# Schematics.net
KiCad netlist of a schematic drawn in EAGLE
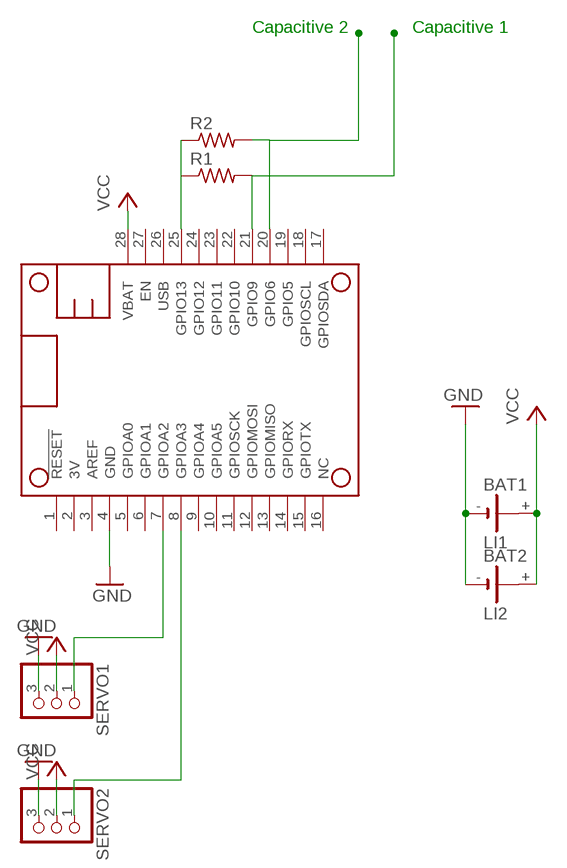
[diagram p0: schematic, sheet 1]

(export (version "E")
  (design (tool "Eeschema 10.0.6"))
  (components
    (comp (ref "BAT1")
      (value "LI1")
      (footprint "eagle-import:CR1_2")
      (libsource (lib "eagle-import") (part "CR1/2"))
    )
    (comp (ref "BAT2")
      (value "LI2")
      (footprint "eagle-import:CR1_2")
      (libsource (lib "eagle-import") (part "CR1/2"))
    )
    (comp (ref "MS1")
      (value "FEATHERWING")
      (footprint "eagle-import:FEATHERWING")
      (libsource (lib "eagle-import") (part "FEATHERWING"))
    )
    (comp (ref "R1")
      (value "R-US_0411/12")
      (footprint "eagle-import:0411_12")
      (libsource (lib "eagle-import") (part "R-US_0411/12"))
    )
    (comp (ref "R2")
      (value "R-US_0411/12")
      (footprint "eagle-import:0411_12")
      (libsource (lib "eagle-import") (part "R-US_0411/12"))
    )
    (comp (ref "SERVO1")
      (value "PINHD-1X3")
      (footprint "eagle-import:1X03")
      (libsource (lib "eagle-import") (part "PINHD-1X3"))
    )
    (comp (ref "SERVO2")
      (value "PINHD-1X3")
      (footprint "eagle-import:1X03")
      (libsource (lib "eagle-import") (part "PINHD-1X3"))
    )
  )
  (nets
    (net (code "1") (name "/3V") (class "Default")
      (node (ref "MS1") (pin "2") (pinfunction "3V_2") (pintype "power_in"))
    )
    (net (code "2") (name "/USB") (class "Default")
      (node (ref "MS1") (pin "26") (pinfunction "USB_26") (pintype "power_in"))
    )
    (net (code "3") (name "GND") (class "Default")
      (node (ref "BAT1") (pin "-") (pinfunction "-_-") (pintype "passive"))
      (node (ref "BAT2") (pin "-") (pinfunction "-_-") (pintype "passive"))
      (node (ref "MS1") (pin "4") (pinfunction "GND_4") (pintype "power_in"))
      (node (ref "SERVO1") (pin "3") (pinfunction "3_3") (pintype "passive"))
      (node (ref "SERVO2") (pin "3") (pinfunction "3_3") (pintype "passive"))
    )
    (net (code "4") (name "Net-(MS1-GPIO6)") (class "Default")
      (node (ref "MS1") (pin "20") (pinfunction "GPIO6_20") (pintype "bidirectional"))
      (node (ref "R2") (pin "2") (pinfunction "2_2") (pintype "passive"))
    )
    (net (code "5") (name "Net-(MS1-GPIO9)") (class "Default")
      (node (ref "MS1") (pin "21") (pinfunction "GPIO9_21") (pintype "bidirectional"))
      (node (ref "R1") (pin "2") (pinfunction "2_2") (pintype "passive"))
    )
    (net (code "6") (name "Net-(MS1-GPIO13)") (class "Default")
      (node (ref "MS1") (pin "25") (pinfunction "GPIO13_25") (pintype "bidirectional"))
      (node (ref "R2") (pin "1") (pinfunction "1_1") (pintype "passive"))
    )
    (net (code "7") (name "Net-(MS1-GPIOA2)") (class "Default")
      (node (ref "MS1") (pin "7") (pinfunction "GPIOA2_7") (pintype "bidirectional"))
      (node (ref "SERVO1") (pin "1") (pinfunction "1_1") (pintype "passive"))
    )
    (net (code "8") (name "Net-(MS1-GPIOA3)") (class "Default")
      (node (ref "MS1") (pin "8") (pinfunction "GPIOA3_8") (pintype "bidirectional"))
      (node (ref "SERVO2") (pin "1") (pinfunction "1_1") (pintype "passive"))
    )
    (net (code "9") (name "VCC") (class "Default")
      (node (ref "BAT1") (pin "+") (pinfunction "+_+") (pintype "passive"))
      (node (ref "BAT2") (pin "+") (pinfunction "+_+") (pintype "passive"))
      (node (ref "MS1") (pin "28") (pinfunction "VBAT_28") (pintype "power_in"))
      (node (ref "SERVO1") (pin "2") (pinfunction "2_2") (pintype "passive"))
      (node (ref "SERVO2") (pin "2") (pinfunction "2_2") (pintype "passive"))
    )
    (net (code "10") (name "unconnected-(BAT1-+-Pad+@1)") (class "Default")
      (node (ref "BAT1") (pin "+@1") (pinfunction "+_+@1") (pintype "passive"))
    )
    (net (code "11") (name "unconnected-(BAT2-+-Pad+@1)") (class "Default")
      (node (ref "BAT2") (pin "+@1") (pinfunction "+_+@1") (pintype "passive"))
    )
    (net (code "12") (name "unconnected-(MS1-AREF-Pad3)") (class "Default")
      (node (ref "MS1") (pin "3") (pinfunction "AREF_3") (pintype "passive"))
    )
    (net (code "13") (name "unconnected-(MS1-EN-Pad27)") (class "Default")
      (node (ref "MS1") (pin "27") (pinfunction "EN_27") (pintype "passive"))
    )
    (net (code "14") (name "unconnected-(MS1-GPIO5-Pad19)") (class "Default")
      (node (ref "MS1") (pin "19") (pinfunction "GPIO5_19") (pintype "bidirectional"))
    )
    (net (code "15") (name "unconnected-(MS1-GPIO10-Pad22)") (class "Default")
      (node (ref "MS1") (pin "22") (pinfunction "GPIO10_22") (pintype "bidirectional"))
    )
    (net (code "16") (name "unconnected-(MS1-GPIO11-Pad23)") (class "Default")
      (node (ref "MS1") (pin "23") (pinfunction "GPIO11_23") (pintype "bidirectional"))
    )
    (net (code "17") (name "unconnected-(MS1-GPIO12-Pad24)") (class "Default")
      (node (ref "MS1") (pin "24") (pinfunction "GPIO12_24") (pintype "bidirectional"))
    )
    (net (code "18") (name "unconnected-(MS1-GPIOA0-Pad5)") (class "Default")
      (node (ref "MS1") (pin "5") (pinfunction "GPIOA0_5") (pintype "bidirectional"))
    )
    (net (code "19") (name "unconnected-(MS1-GPIOA1-Pad6)") (class "Default")
      (node (ref "MS1") (pin "6") (pinfunction "GPIOA1_6") (pintype "bidirectional"))
    )
    (net (code "20") (name "unconnected-(MS1-GPIOA4-Pad9)") (class "Default")
      (node (ref "MS1") (pin "9") (pinfunction "GPIOA4_9") (pintype "bidirectional"))
    )
    (net (code "21") (name "unconnected-(MS1-GPIOA5-Pad10)") (class "Default")
      (node (ref "MS1") (pin "10") (pinfunction "GPIOA5_10") (pintype "bidirectional"))
    )
    (net (code "22") (name "unconnected-(MS1-GPIOMISO-Pad13)") (class "Default")
      (node (ref "MS1") (pin "13") (pinfunction "GPIOMISO_13") (pintype "bidirectional"))
    )
    (net (code "23") (name "unconnected-(MS1-GPIOMOSI-Pad12)") (class "Default")
      (node (ref "MS1") (pin "12") (pinfunction "GPIOMOSI_12") (pintype "bidirectional"))
    )
    (net (code "24") (name "unconnected-(MS1-GPIORX-Pad14)") (class "Default")
      (node (ref "MS1") (pin "14") (pinfunction "GPIORX_14") (pintype "bidirectional"))
    )
    (net (code "25") (name "unconnected-(MS1-GPIOSCK-Pad11)") (class "Default")
      (node (ref "MS1") (pin "11") (pinfunction "GPIOSCK_11") (pintype "bidirectional"))
    )
    (net (code "26") (name "unconnected-(MS1-GPIOSCL-Pad18)") (class "Default")
      (node (ref "MS1") (pin "18") (pinfunction "GPIOSCL_18") (pintype "bidirectional"))
    )
    (net (code "27") (name "unconnected-(MS1-GPIOSDA-Pad17)") (class "Default")
      (node (ref "MS1") (pin "17") (pinfunction "GPIOSDA_17") (pintype "bidirectional"))
    )
    (net (code "28") (name "unconnected-(MS1-GPIOTX-Pad15)") (class "Default")
      (node (ref "MS1") (pin "15") (pinfunction "GPIOTX_15") (pintype "bidirectional"))
    )
    (net (code "29") (name "unconnected-(MS1-NC-Pad16)") (class "Default")
      (node (ref "MS1") (pin "16") (pinfunction "NC_16") (pintype "passive"))
    )
    (net (code "30") (name "unconnected-(MS1-~{RESET}-Pad1)") (class "Default")
      (node (ref "MS1") (pin "1") (pinfunction "~{RESET}_1") (pintype "input"))
    )
    (net (code "31") (name "unconnected-(R1-Pad1)") (class "Default")
      (node (ref "R1") (pin "1") (pinfunction "1_1") (pintype "passive"))
    )
  )
)
